# Input.net
KiCad netlist of a schematic drawn in Altium Designer
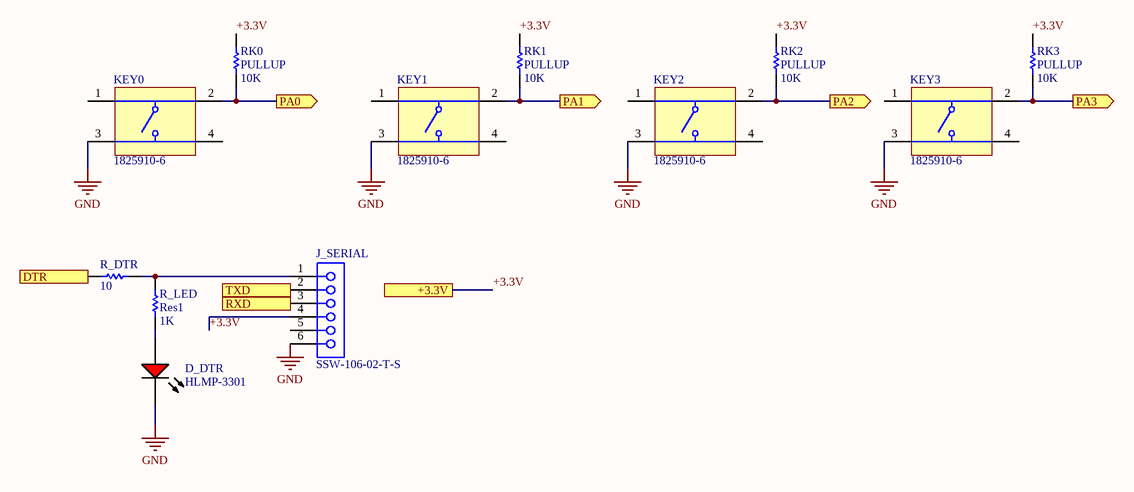
[diagram p0: Input.SchDoc]

(export (version "E")
  (design (tool "Eeschema 10.0.6"))
  (components
    (comp (ref "D_DTR")
      (value "HLMP-3301")
      (footprint "AVAG-HLMP-3301-2")
      (description "T-1 3/4 (5 mm) Diffused LED Lamp, 1.9 V, -40 to 100 degC, 2-Pin THD, RoHS, Bulk")
      (fields (field (name "MANUFACTURER") "Avago"))
      (libsource (lib "Altium Content Vault") (part "LED-RED-K1A2-2"))
    )
    (comp (ref "J_SERIAL")
      (value "SSW-106-02-T-S")
      (footprint "SMTC-SSW-106-02-X-S")
      (description "SQ Post Socket, Through-hole, Vertical, -55 to 105 degC, 2.54mm Pitch, 6-Pin, Female, RoHS")
      (fields (field (name "MANUFACTURER") "Samtec"))
      (libsource (lib "Altium Content Vault") (part "SMTC-SSW-106-02-X-S-X"))
    )
    (comp (ref "KEY0")
      (value "1825910-6")
      (footprint "TECO-1825910-6_V")
      (description "Tact Switch, SPST-NO, 0.05 A, -35 to 85 degC, 4-Pin THD, RoHS, Bulk")
      (fields (field (name "MANUFACTURER") "TE Connectivity"))
      (libsource (lib "Altium Content Vault") (part "SW-SPST-4_A"))
    )
    (comp (ref "KEY1")
      (value "1825910-6")
      (footprint "TECO-1825910-6_V")
      (description "Tact Switch, SPST-NO, 0.05 A, -35 to 85 degC, 4-Pin THD, RoHS, Bulk")
      (fields (field (name "MANUFACTURER") "TE Connectivity"))
      (libsource (lib "Altium Content Vault") (part "SW-SPST-4_A"))
    )
    (comp (ref "KEY2")
      (value "1825910-6")
      (footprint "TECO-1825910-6_V")
      (description "Tact Switch, SPST-NO, 0.05 A, -35 to 85 degC, 4-Pin THD, RoHS, Bulk")
      (fields (field (name "MANUFACTURER") "TE Connectivity"))
      (libsource (lib "Altium Content Vault") (part "SW-SPST-4_A"))
    )
    (comp (ref "KEY3")
      (value "1825910-6")
      (footprint "TECO-1825910-6_V")
      (description "Tact Switch, SPST-NO, 0.05 A, -35 to 85 degC, 4-Pin THD, RoHS, Bulk")
      (fields (field (name "MANUFACTURER") "TE Connectivity"))
      (libsource (lib "Altium Content Vault") (part "SW-SPST-4_A"))
    )
    (comp (ref "RK0")
      (value "PULLUP")
      (footprint "AXIAL-0.1-RES")
      (description "Resistor")
      (fields
        (field (name "ALTIUM_VALUE") "10K")
        (field (name "MANUFACTURER PART NUMBER") "CFR-25JB-52-10K")
        (field (name "TOLERANCE") "0.05")
        (field (name "PUBLISHER") "Altium Limited")
      )
      (libsource (lib "ECE295-Resistors-TH") (part "RES 10K OHM 5% 1/4W AXIAL"))
    )
    (comp (ref "RK1")
      (value "PULLUP")
      (footprint "AXIAL-0.1-RES")
      (description "Resistor")
      (fields
        (field (name "ALTIUM_VALUE") "10K")
        (field (name "MANUFACTURER PART NUMBER") "CFR-25JB-52-10K")
        (field (name "TOLERANCE") "0.05")
        (field (name "PUBLISHER") "Altium Limited")
      )
      (libsource (lib "ECE295-Resistors-TH") (part "RES 10K OHM 5% 1/4W AXIAL"))
    )
    (comp (ref "RK2")
      (value "PULLUP")
      (footprint "AXIAL-0.1-RES")
      (description "Resistor")
      (fields
        (field (name "ALTIUM_VALUE") "10K")
        (field (name "MANUFACTURER PART NUMBER") "CFR-25JB-52-10K")
        (field (name "TOLERANCE") "0.05")
        (field (name "PUBLISHER") "Altium Limited")
      )
      (libsource (lib "ECE295-Resistors-TH") (part "RES 10K OHM 5% 1/4W AXIAL"))
    )
    (comp (ref "RK3")
      (value "PULLUP")
      (footprint "AXIAL-0.1-RES")
      (description "Resistor")
      (fields
        (field (name "ALTIUM_VALUE") "10K")
        (field (name "MANUFACTURER PART NUMBER") "CFR-25JB-52-10K")
        (field (name "TOLERANCE") "0.05")
        (field (name "PUBLISHER") "Altium Limited")
      )
      (libsource (lib "ECE295-Resistors-TH") (part "RES 10K OHM 5% 1/4W AXIAL"))
    )
    (comp (ref "R_DTR")
      (value "10")
      (footprint "AXIAL-0.1-RES")
      (description "Resistor")
      (fields
        (field (name "MANUFACTURER PART NUMBER") "CFR-25JB-52-10R")
        (field (name "TOLERANCE") "0.05")
        (field (name "PUBLISHER") "Altium Limited")
      )
      (libsource (lib "ECE295-Resistors-TH") (part "RES 10 OHM 5% 1/4W AXIAL"))
    )
    (comp (ref "R_LED")
      (value "Res1")
      (footprint "AXIAL-0.1-RES")
      (description "Resistor")
      (fields
        (field (name "MANUFACTURER PART NUMBER") "CFR-25JB-52-1K")
        (field (name "TOLERANCE") "0.05")
        (field (name "ALTIUM_VALUE") "1K")
        (field (name "PUBLISHER") "Altium Limited")
      )
      (libsource (lib "ECE295-Resistors-TH") (part "RES 1K OHM 5% 1/4W AXIAL"))
    )
  )
  (nets
    (net (code "1") (name "/+3.3V") (class "Default")
      (node (ref "J_SERIAL") (pin "4") (pinfunction "4_4") (pintype "passive"))
      (node (ref "RK0") (pin "2") (pinfunction "2_2") (pintype "passive"))
      (node (ref "RK1") (pin "2") (pinfunction "2_2") (pintype "passive"))
      (node (ref "RK2") (pin "2") (pinfunction "2_2") (pintype "passive"))
      (node (ref "RK3") (pin "2") (pinfunction "2_2") (pintype "passive"))
    )
    (net (code "2") (name "/DTR") (class "Default")
      (node (ref "R_DTR") (pin "1") (pinfunction "1_1") (pintype "passive"))
    )
    (net (code "3") (name "/PA0") (class "Default")
      (node (ref "KEY0") (pin "2") (pinfunction "2_2") (pintype "passive"))
      (node (ref "RK0") (pin "1") (pinfunction "1_1") (pintype "passive"))
    )
    (net (code "4") (name "/PA1") (class "Default")
      (node (ref "KEY1") (pin "2") (pinfunction "2_2") (pintype "passive"))
      (node (ref "RK1") (pin "1") (pinfunction "1_1") (pintype "passive"))
    )
    (net (code "5") (name "/PA2") (class "Default")
      (node (ref "KEY2") (pin "2") (pinfunction "2_2") (pintype "passive"))
      (node (ref "RK2") (pin "1") (pinfunction "1_1") (pintype "passive"))
    )
    (net (code "6") (name "/PA3") (class "Default")
      (node (ref "KEY3") (pin "2") (pinfunction "2_2") (pintype "passive"))
      (node (ref "RK3") (pin "1") (pinfunction "1_1") (pintype "passive"))
    )
    (net (code "7") (name "/RXD") (class "Default")
      (node (ref "J_SERIAL") (pin "3") (pinfunction "3_3") (pintype "passive"))
    )
    (net (code "8") (name "/TXD") (class "Default")
      (node (ref "J_SERIAL") (pin "2") (pinfunction "2_2") (pintype "passive"))
    )
    (net (code "9") (name "GND") (class "Default")
      (node (ref "D_DTR") (pin "1") (pinfunction "K_1") (pintype "passive"))
      (node (ref "J_SERIAL") (pin "6") (pinfunction "6_6") (pintype "passive"))
      (node (ref "KEY0") (pin "3") (pinfunction "3_3") (pintype "passive"))
      (node (ref "KEY1") (pin "3") (pinfunction "3_3") (pintype "passive"))
      (node (ref "KEY2") (pin "3") (pinfunction "3_3") (pintype "passive"))
      (node (ref "KEY3") (pin "3") (pinfunction "3_3") (pintype "passive"))
    )
    (net (code "10") (name "Net-(D_DTR-A)") (class "Default")
      (node (ref "D_DTR") (pin "2") (pinfunction "A_2") (pintype "passive"))
      (node (ref "R_LED") (pin "1") (pinfunction "1_1") (pintype "passive"))
    )
    (net (code "11") (name "Net-(J_SERIAL-Pad1)") (class "Default")
      (node (ref "J_SERIAL") (pin "1") (pinfunction "1_1") (pintype "passive"))
      (node (ref "R_DTR") (pin "2") (pinfunction "2_2") (pintype "passive"))
      (node (ref "R_LED") (pin "2") (pinfunction "2_2") (pintype "passive"))
    )
    (net (code "12") (name "unconnected-(J_SERIAL-Pad5)") (class "Default")
      (node (ref "J_SERIAL") (pin "5") (pinfunction "5_5") (pintype "passive"))
    )
    (net (code "13") (name "unconnected-(KEY0-Pad1)") (class "Default")
      (node (ref "KEY0") (pin "1") (pinfunction "1_1") (pintype "passive"))
    )
    (net (code "14") (name "unconnected-(KEY0-Pad4)") (class "Default")
      (node (ref "KEY0") (pin "4") (pinfunction "4_4") (pintype "passive"))
    )
    (net (code "15") (name "unconnected-(KEY1-Pad1)") (class "Default")
      (node (ref "KEY1") (pin "1") (pinfunction "1_1") (pintype "passive"))
    )
    (net (code "16") (name "unconnected-(KEY1-Pad4)") (class "Default")
      (node (ref "KEY1") (pin "4") (pinfunction "4_4") (pintype "passive"))
    )
    (net (code "17") (name "unconnected-(KEY2-Pad1)") (class "Default")
      (node (ref "KEY2") (pin "1") (pinfunction "1_1") (pintype "passive"))
    )
    (net (code "18") (name "unconnected-(KEY2-Pad4)") (class "Default")
      (node (ref "KEY2") (pin "4") (pinfunction "4_4") (pintype "passive"))
    )
    (net (code "19") (name "unconnected-(KEY3-Pad1)") (class "Default")
      (node (ref "KEY3") (pin "1") (pinfunction "1_1") (pintype "passive"))
    )
    (net (code "20") (name "unconnected-(KEY3-Pad4)") (class "Default")
      (node (ref "KEY3") (pin "4") (pinfunction "4_4") (pintype "passive"))
    )
  )
)
